# Power.net
KiCad netlist of a schematic drawn in Altium Designer
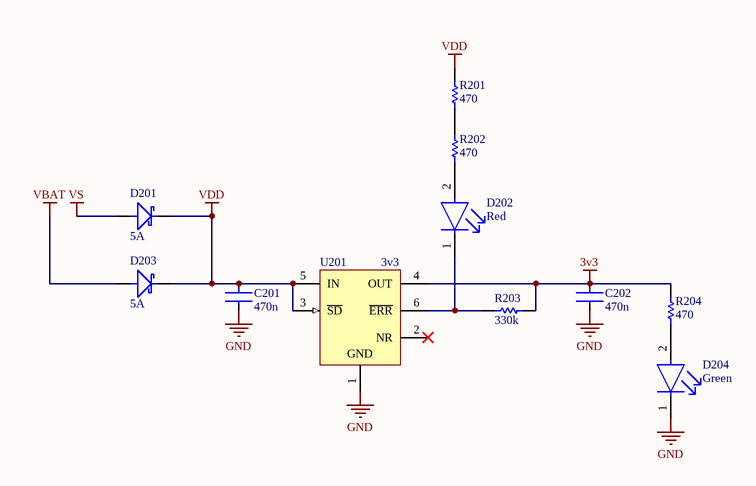
[diagram p0: Power.SchDoc]

(export (version "E")
  (design (tool "Eeschema 10.0.6"))
  (components
    (comp (ref "C201")
      (value "470n")
      (footprint "FP-GRT155-0_05-MFG")
      (description "Multi-Layer Ceramic Capacitor 470nF 25V X5R ±10% 0402 Paper T/R")
      (fields (field (name "TOLERANCE") "10%"))
      (libsource (lib "Main") (part "GRT155R61E474KE01D"))
    )
    (comp (ref "C202")
      (value "470n")
      (footprint "FP-GRT155-0_05-MFG")
      (description "Multi-Layer Ceramic Capacitor 470nF 25V X5R ±10% 0402 Paper T/R")
      (fields (field (name "TOLERANCE") "10%"))
      (libsource (lib "Main") (part "GRT155R61E474KE01D"))
    )
    (comp (ref "D201")
      (value "5A")
      (footprint "SODFL470X105-2L")
      (libsource (lib "Main") (part "RB080LAM-30TR"))
    )
    (comp (ref "D202")
      (value "Red")
      (footprint "FP-SML-P1-MFG")
      (description "LED RED CLEAR 1006 SMD")
      (fields (field (name "MANUFACTURER") "Rohm") (field (name "MANUFACTURER PART NUMBER") "SML-P11UTT86R"))
      (libsource (lib "Main") (part "SML-P11UTT86R"))
    )
    (comp (ref "D203")
      (value "5A")
      (footprint "SODFL470X105-2L")
      (libsource (lib "Main") (part "RB080LAM-30TR"))
    )
    (comp (ref "D204")
      (value "Green")
      (footprint "FP-SML-P1-MFG")
      (description "LED GREEN CLEAR 1006 SMD")
      (fields (field (name "MANUFACTURER PART NUMBER") "SML-P13PTT86R") (field (name "MANUFACTURER") "Rohm"))
      (libsource (lib "Main") (part "SML-P13PTT86R"))
    )
    (comp (ref "R201")
      (value "470")
      (footprint "RESC1005X04N")
      (fields (field (name "MANUFACTURER") "Panasonic") (field (name "PART NUMBER") "ERJ2RKF27R0X"))
      (libsource (lib "Main") (part "ERJ-U02J471X"))
    )
    (comp (ref "R202")
      (value "470")
      (footprint "RESC1005X04N")
      (fields (field (name "MANUFACTURER") "Panasonic") (field (name "PART NUMBER") "ERJ2RKF27R0X"))
      (libsource (lib "Main") (part "ERJ-U02J471X"))
    )
    (comp (ref "R203")
      (value "330k")
      (footprint "RESC1005X04N")
      (fields (field (name "MANUFACTURER") "Panasonic") (field (name "PART NUMBER") "ERJ2RKF27R0X"))
      (libsource (lib "Main") (part "ERJ-2GEJ334X"))
    )
    (comp (ref "R204")
      (value "470")
      (footprint "RESC1005X04N")
      (fields (field (name "MANUFACTURER") "Panasonic") (field (name "PART NUMBER") "ERJ2RKF27R0X"))
      (libsource (lib "Main") (part "ERJ-U02J471X"))
    )
    (comp (ref "U201")
      (value "3v3")
      (footprint "SOT95P280X145-6L")
      (fields (field (name "MANUFACTURER") "Analog Devices") (field (name "PARTNUMBER") "ADP3300ARTZ-3.3RL7"))
      (libsource (lib "Main") (part "ADP3300ARTZ-3.3RL7"))
    )
  )
  (nets
    (net (code "1") (name "3v3") (class "Default")
      (node (ref "C202") (pin "1") (pinfunction "1_1") (pintype "passive"))
      (node (ref "R203") (pin "1") (pinfunction "1_1") (pintype "passive"))
      (node (ref "R204") (pin "2") (pinfunction "2_2") (pintype "passive"))
      (node (ref "U201") (pin "4") (pinfunction "OUT_4") (pintype "power_in"))
    )
    (net (code "2") (name "GND") (class "Default")
      (node (ref "C201") (pin "2") (pinfunction "2_2") (pintype "passive"))
      (node (ref "C202") (pin "2") (pinfunction "2_2") (pintype "passive"))
      (node (ref "D204") (pin "1") (pinfunction "C_1") (pintype "passive"))
      (node (ref "U201") (pin "1") (pinfunction "GND_1") (pintype "power_in"))
    )
    (net (code "3") (name "Net-(D202-A)") (class "Default")
      (node (ref "D202") (pin "2") (pinfunction "A_2") (pintype "passive"))
      (node (ref "R202") (pin "1") (pinfunction "1_1") (pintype "passive"))
    )
    (net (code "4") (name "Net-(D202-C)") (class "Default")
      (node (ref "D202") (pin "1") (pinfunction "C_1") (pintype "passive"))
      (node (ref "R203") (pin "2") (pinfunction "2_2") (pintype "passive"))
      (node (ref "U201") (pin "6") (pinfunction "~{ERR}_6") (pintype "open_collector"))
    )
    (net (code "5") (name "Net-(D204-A)") (class "Default")
      (node (ref "D204") (pin "2") (pinfunction "A_2") (pintype "passive"))
      (node (ref "R204") (pin "1") (pinfunction "1_1") (pintype "passive"))
    )
    (net (code "6") (name "Net-(R201-Pad1)") (class "Default")
      (node (ref "R201") (pin "1") (pinfunction "1_1") (pintype "passive"))
      (node (ref "R202") (pin "2") (pinfunction "2_2") (pintype "passive"))
    )
    (net (code "7") (name "VBAT") (class "Default")
      (node (ref "D203") (pin "2") (pinfunction "2_2") (pintype "power_in"))
    )
    (net (code "8") (name "VDD") (class "Default")
      (node (ref "C201") (pin "1") (pinfunction "1_1") (pintype "passive"))
      (node (ref "D201") (pin "1") (pinfunction "1_1") (pintype "power_in"))
      (node (ref "D203") (pin "1") (pinfunction "1_1") (pintype "power_in"))
      (node (ref "R201") (pin "2") (pinfunction "2_2") (pintype "passive"))
      (node (ref "U201") (pin "3") (pinfunction "~{SD}_3") (pintype "input"))
      (node (ref "U201") (pin "5") (pinfunction "IN_5") (pintype "power_in"))
    )
    (net (code "9") (name "VS") (class "Default")
      (node (ref "D201") (pin "2") (pinfunction "2_2") (pintype "power_in"))
    )
    (net (code "10") (name "unconnected-(U201-NR-Pad2)") (class "Default")
      (node (ref "U201") (pin "2") (pinfunction "NR_2") (pintype "passive+no_connect"))
    )
  )
)
